# Porta_MDB.net
KiCad netlist of a schematic drawn in Altium Designer
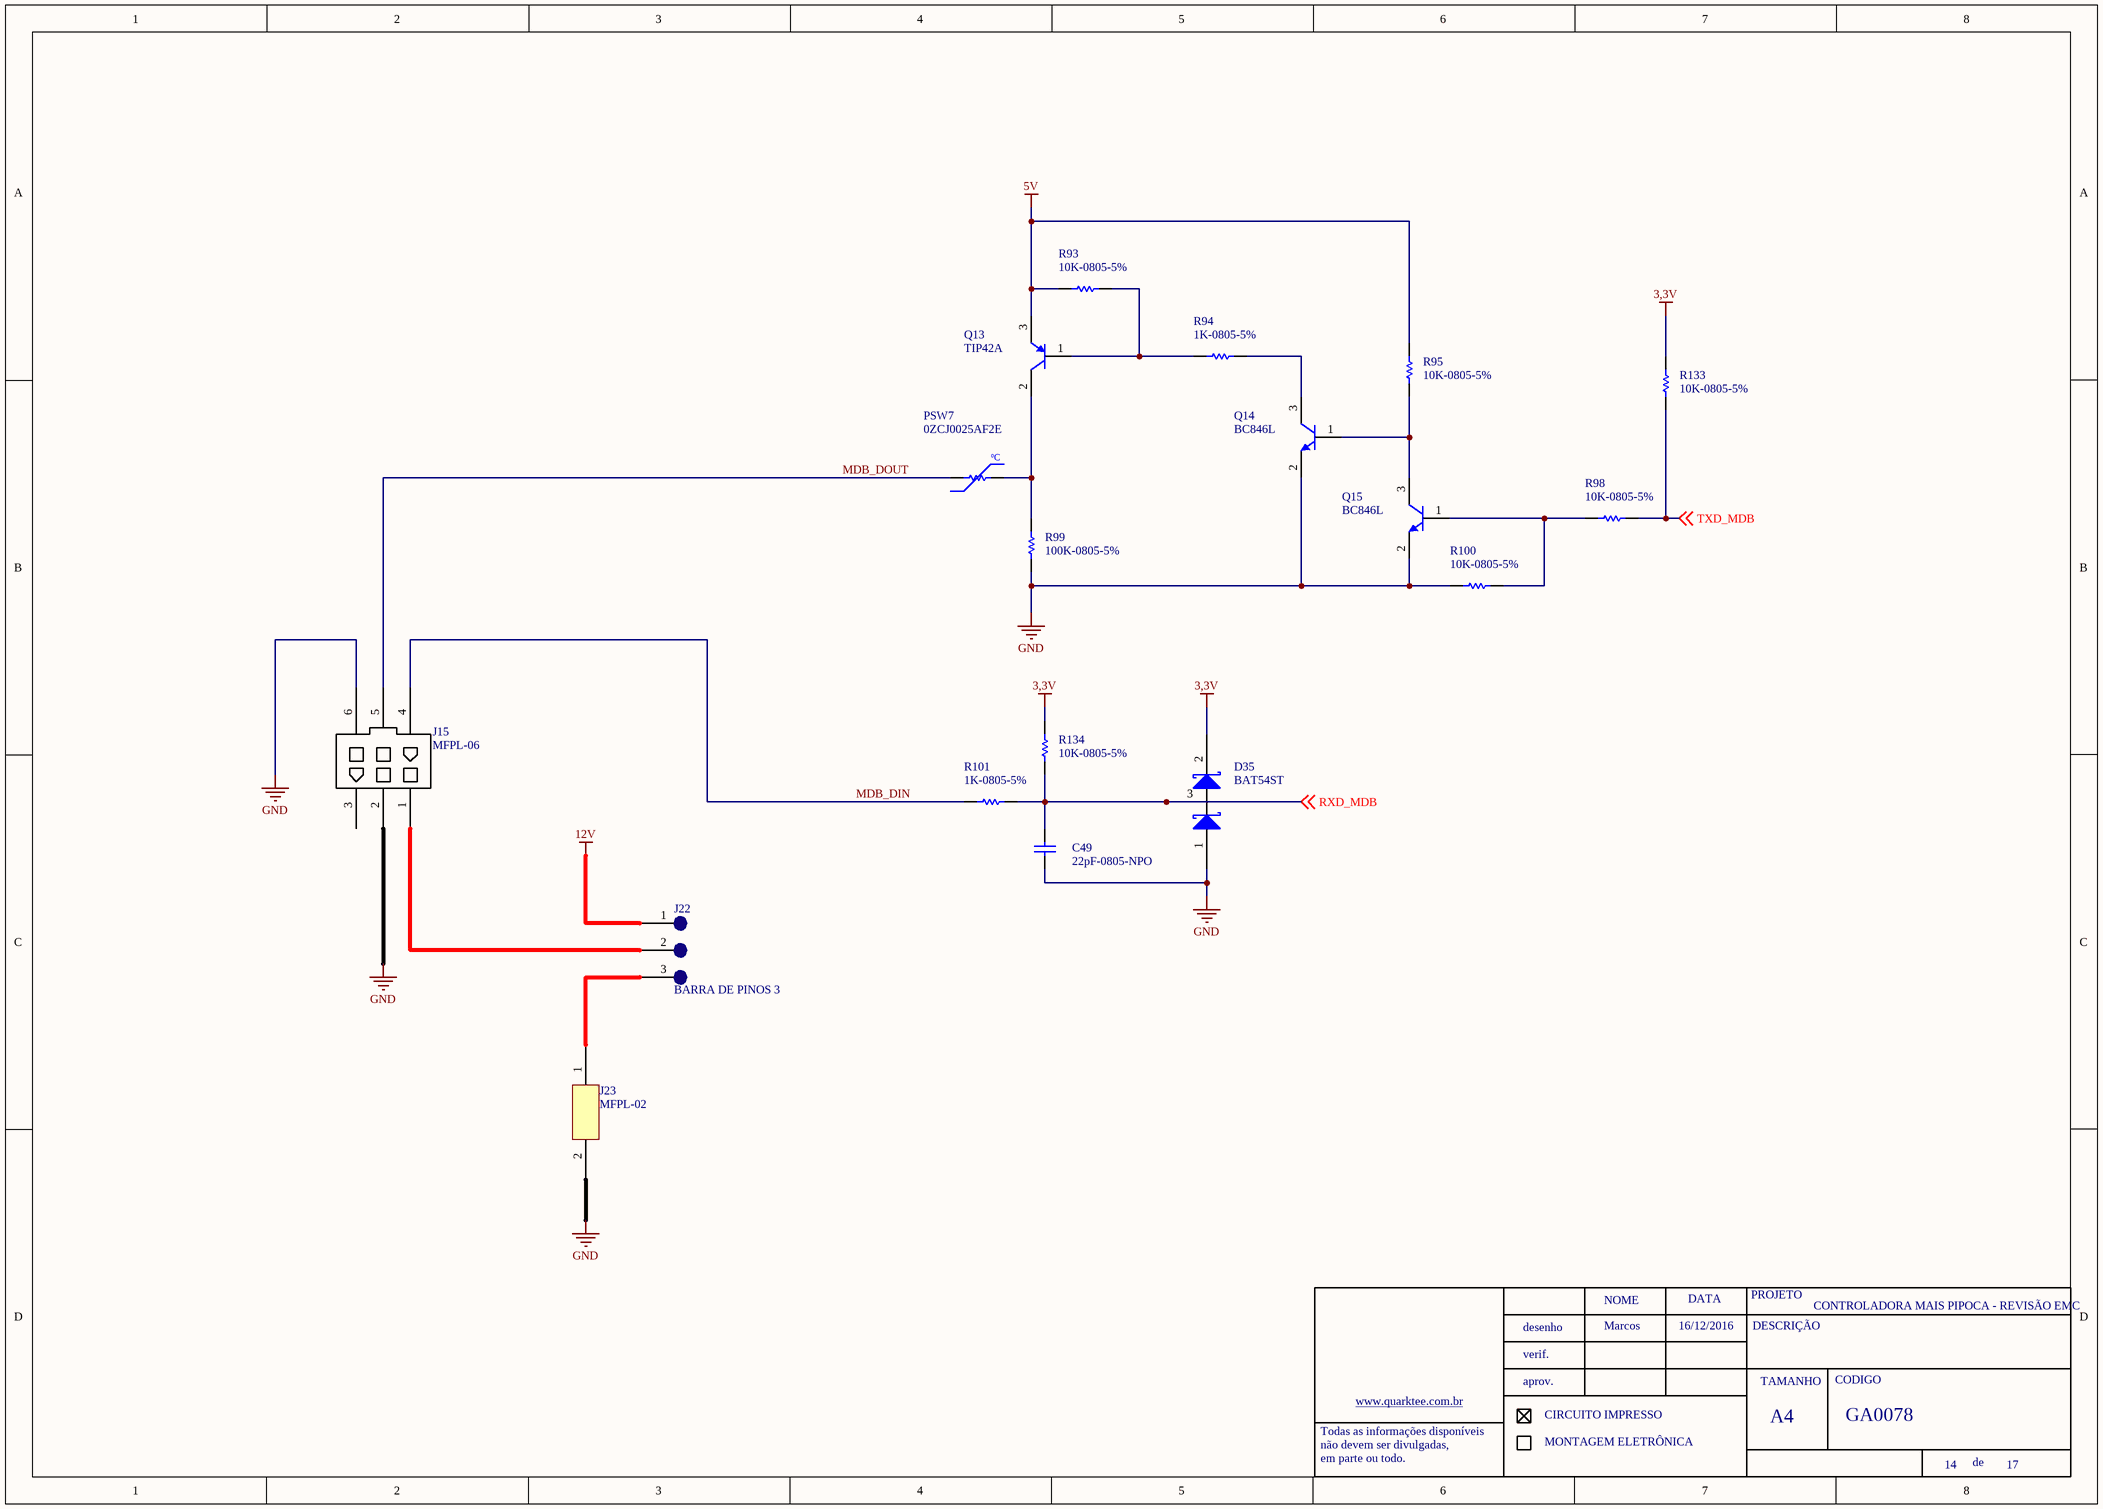
[diagram p0: Porta_MDB.SchDoc]

(export (version "E")
  (design (tool "Eeschema 10.0.6"))
  (components
    (comp (ref "C49")
      (value "22pF-0805-NPO")
      (footprint "0805-REVISADO ONDA")
      (libsource (lib "AquinoLib") (part "22pF-0805-NPO"))
    )
    (comp (ref "D35")
      (value "BAT54ST")
      (footprint "SOT23 - REVISADO ONDA")
      (libsource (lib "AquinoLib") (part "BAT54ST"))
    )
    (comp (ref "J15") (value "MFPL-06") (libsource (lib "AquinoLib") (part "MFPL-06")))
    (comp (ref "J22") (value "BARRA DE PINOS 3") (libsource (lib "ChaveDigital3") (part "JUMPER 3")))
    (comp (ref "J23") (value "MFPL-02") (libsource (lib "AquinoLib") (part "MFPL-02")))
    (comp (ref "PSW7")
      (value "0ZCJ0025AF2E")
      (footprint "1206-REVISADO ONDA")
      (description "PTC 2A-120V")
      (libsource (lib "AquinoLib") (part "PTC 2A-120V"))
    )
    (comp (ref "Q13")
      (value "TIP42A")
      (footprint "DPAK REVISADO ONDA")
      (libsource (lib "AquinoLib") (part "TIP42A"))
    )
    (comp (ref "Q14")
      (value "BC846L")
      (footprint "SOT23 - REVISADO ONDA")
      (libsource (lib "AquinoLib") (part "BC846"))
    )
    (comp (ref "Q15")
      (value "BC846L")
      (footprint "SOT23 - REVISADO ONDA")
      (libsource (lib "AquinoLib") (part "BC846"))
    )
    (comp (ref "R93")
      (value "10K-0805-5%")
      (footprint "0805-REVISADO ONDA")
      (libsource (lib "AquinoLib") (part "10K-0805-5%"))
    )
    (comp (ref "R94")
      (value "1K-0805-5%")
      (footprint "0805-REVISADO ONDA")
      (libsource (lib "AquinoLib") (part "1K-0805-5%"))
    )
    (comp (ref "R95")
      (value "10K-0805-5%")
      (footprint "0805-REVISADO ONDA")
      (libsource (lib "AquinoLib") (part "10K-0805-5%"))
    )
    (comp (ref "R98")
      (value "10K-0805-5%")
      (footprint "0805-REVISADO ONDA")
      (libsource (lib "AquinoLib") (part "10K-0805-5%"))
    )
    (comp (ref "R99")
      (value "100K-0805-5%")
      (footprint "0805-REVISADO ONDA")
      (libsource (lib "AquinoLib") (part "100K-0805-5%"))
    )
    (comp (ref "R100")
      (value "10K-0805-5%")
      (footprint "0805-REVISADO ONDA")
      (libsource (lib "AquinoLib") (part "10K-0805-5%"))
    )
    (comp (ref "R101")
      (value "1K-0805-5%")
      (footprint "0805-REVISADO ONDA")
      (libsource (lib "AquinoLib") (part "1K-0805-5%"))
    )
    (comp (ref "R133")
      (value "10K-0805-5%")
      (footprint "0805-REVISADO ONDA")
      (libsource (lib "AquinoLib") (part "10K-0805-5%"))
    )
    (comp (ref "R134")
      (value "10K-0805-5%")
      (footprint "0805-REVISADO ONDA")
      (libsource (lib "AquinoLib") (part "10K-0805-5%"))
    )
  )
  (nets
    (net (code "1") (name "/MDB_DIN") (class "Default")
      (node (ref "J15") (pin "4") (pinfunction "4_4") (pintype "passive"))
      (node (ref "R101") (pin "1") (pinfunction "1_1") (pintype "passive"))
    )
    (net (code "2") (name "/MDB_DOUT") (class "Default")
      (node (ref "J15") (pin "5") (pinfunction "5_5") (pintype "passive"))
      (node (ref "PSW7") (pin "1") (pinfunction "1_1") (pintype "passive"))
    )
    (net (code "3") (name "3,3V") (class "Default")
      (node (ref "D35") (pin "2") (pinfunction "2_2") (pintype "passive"))
      (node (ref "R133") (pin "2") (pinfunction "2_2") (pintype "passive"))
      (node (ref "R134") (pin "2") (pinfunction "2_2") (pintype "passive"))
    )
    (net (code "4") (name "5V") (class "Default")
      (node (ref "Q13") (pin "3") (pinfunction "E_3") (pintype "passive"))
      (node (ref "R93") (pin "1") (pinfunction "1_1") (pintype "passive"))
      (node (ref "R95") (pin "2") (pinfunction "2_2") (pintype "passive"))
    )
    (net (code "5") (name "12V") (class "Default")
      (node (ref "J22") (pin "1") (pinfunction "1_1") (pintype "passive"))
    )
    (net (code "6") (name "GND") (class "Default")
      (node (ref "C49") (pin "1") (pinfunction "1_1") (pintype "passive"))
      (node (ref "D35") (pin "1") (pinfunction "1_1") (pintype "passive"))
      (node (ref "J15") (pin "2") (pinfunction "2_2") (pintype "passive"))
      (node (ref "J15") (pin "6") (pinfunction "6_6") (pintype "passive"))
      (node (ref "J23") (pin "2") (pinfunction "2_2") (pintype "passive"))
      (node (ref "Q14") (pin "2") (pinfunction "E_2") (pintype "passive"))
      (node (ref "Q15") (pin "2") (pinfunction "E_2") (pintype "passive"))
      (node (ref "R100") (pin "1") (pinfunction "1_1") (pintype "passive"))
      (node (ref "R99") (pin "1") (pinfunction "1_1") (pintype "passive"))
    )
    (net (code "7") (name "Net-(J15-Pad1)") (class "Default")
      (node (ref "J15") (pin "1") (pinfunction "1_1") (pintype "passive"))
      (node (ref "J22") (pin "2") (pinfunction "2_2") (pintype "passive"))
    )
    (net (code "8") (name "Net-(J22-Pad3)") (class "Default")
      (node (ref "J22") (pin "3") (pinfunction "3_3") (pintype "passive"))
      (node (ref "J23") (pin "1") (pinfunction "1_1") (pintype "passive"))
    )
    (net (code "9") (name "Net-(Q13-B)") (class "Default")
      (node (ref "Q13") (pin "1") (pinfunction "B_1") (pintype "passive"))
      (node (ref "R93") (pin "2") (pinfunction "2_2") (pintype "passive"))
      (node (ref "R94") (pin "1") (pinfunction "1_1") (pintype "passive"))
    )
    (net (code "10") (name "Net-(Q13-C)") (class "Default")
      (node (ref "PSW7") (pin "2") (pinfunction "2_2") (pintype "passive"))
      (node (ref "Q13") (pin "2") (pinfunction "C_2") (pintype "passive"))
      (node (ref "R99") (pin "2") (pinfunction "2_2") (pintype "passive"))
    )
    (net (code "11") (name "Net-(Q14-B)") (class "Default")
      (node (ref "Q14") (pin "1") (pinfunction "B_1") (pintype "passive"))
      (node (ref "Q15") (pin "3") (pinfunction "C_3") (pintype "passive"))
      (node (ref "R95") (pin "1") (pinfunction "1_1") (pintype "passive"))
    )
    (net (code "12") (name "Net-(Q14-C)") (class "Default")
      (node (ref "Q14") (pin "3") (pinfunction "C_3") (pintype "passive"))
      (node (ref "R94") (pin "2") (pinfunction "2_2") (pintype "passive"))
    )
    (net (code "13") (name "Net-(Q15-B)") (class "Default")
      (node (ref "Q15") (pin "1") (pinfunction "B_1") (pintype "passive"))
      (node (ref "R100") (pin "2") (pinfunction "2_2") (pintype "passive"))
      (node (ref "R98") (pin "1") (pinfunction "1_1") (pintype "passive"))
    )
    (net (code "14") (name "RXD_MDB") (class "Default")
      (node (ref "C49") (pin "2") (pinfunction "2_2") (pintype "passive"))
      (node (ref "D35") (pin "3") (pinfunction "3_3") (pintype "passive"))
      (node (ref "R101") (pin "2") (pinfunction "2_2") (pintype "passive"))
      (node (ref "R134") (pin "1") (pinfunction "1_1") (pintype "passive"))
    )
    (net (code "15") (name "TXD_MDB") (class "Default")
      (node (ref "R133") (pin "1") (pinfunction "1_1") (pintype "passive"))
      (node (ref "R98") (pin "2") (pinfunction "2_2") (pintype "passive"))
    )
    (net (code "16") (name "unconnected-(J15-Pad3)") (class "Default")
      (node (ref "J15") (pin "3") (pinfunction "3_3") (pintype "passive"))
    )
  )
)
